# SCH_Shape-Of-Sound_2025-08-21.net
KiCad netlist of a schematic drawn in EasyEDA
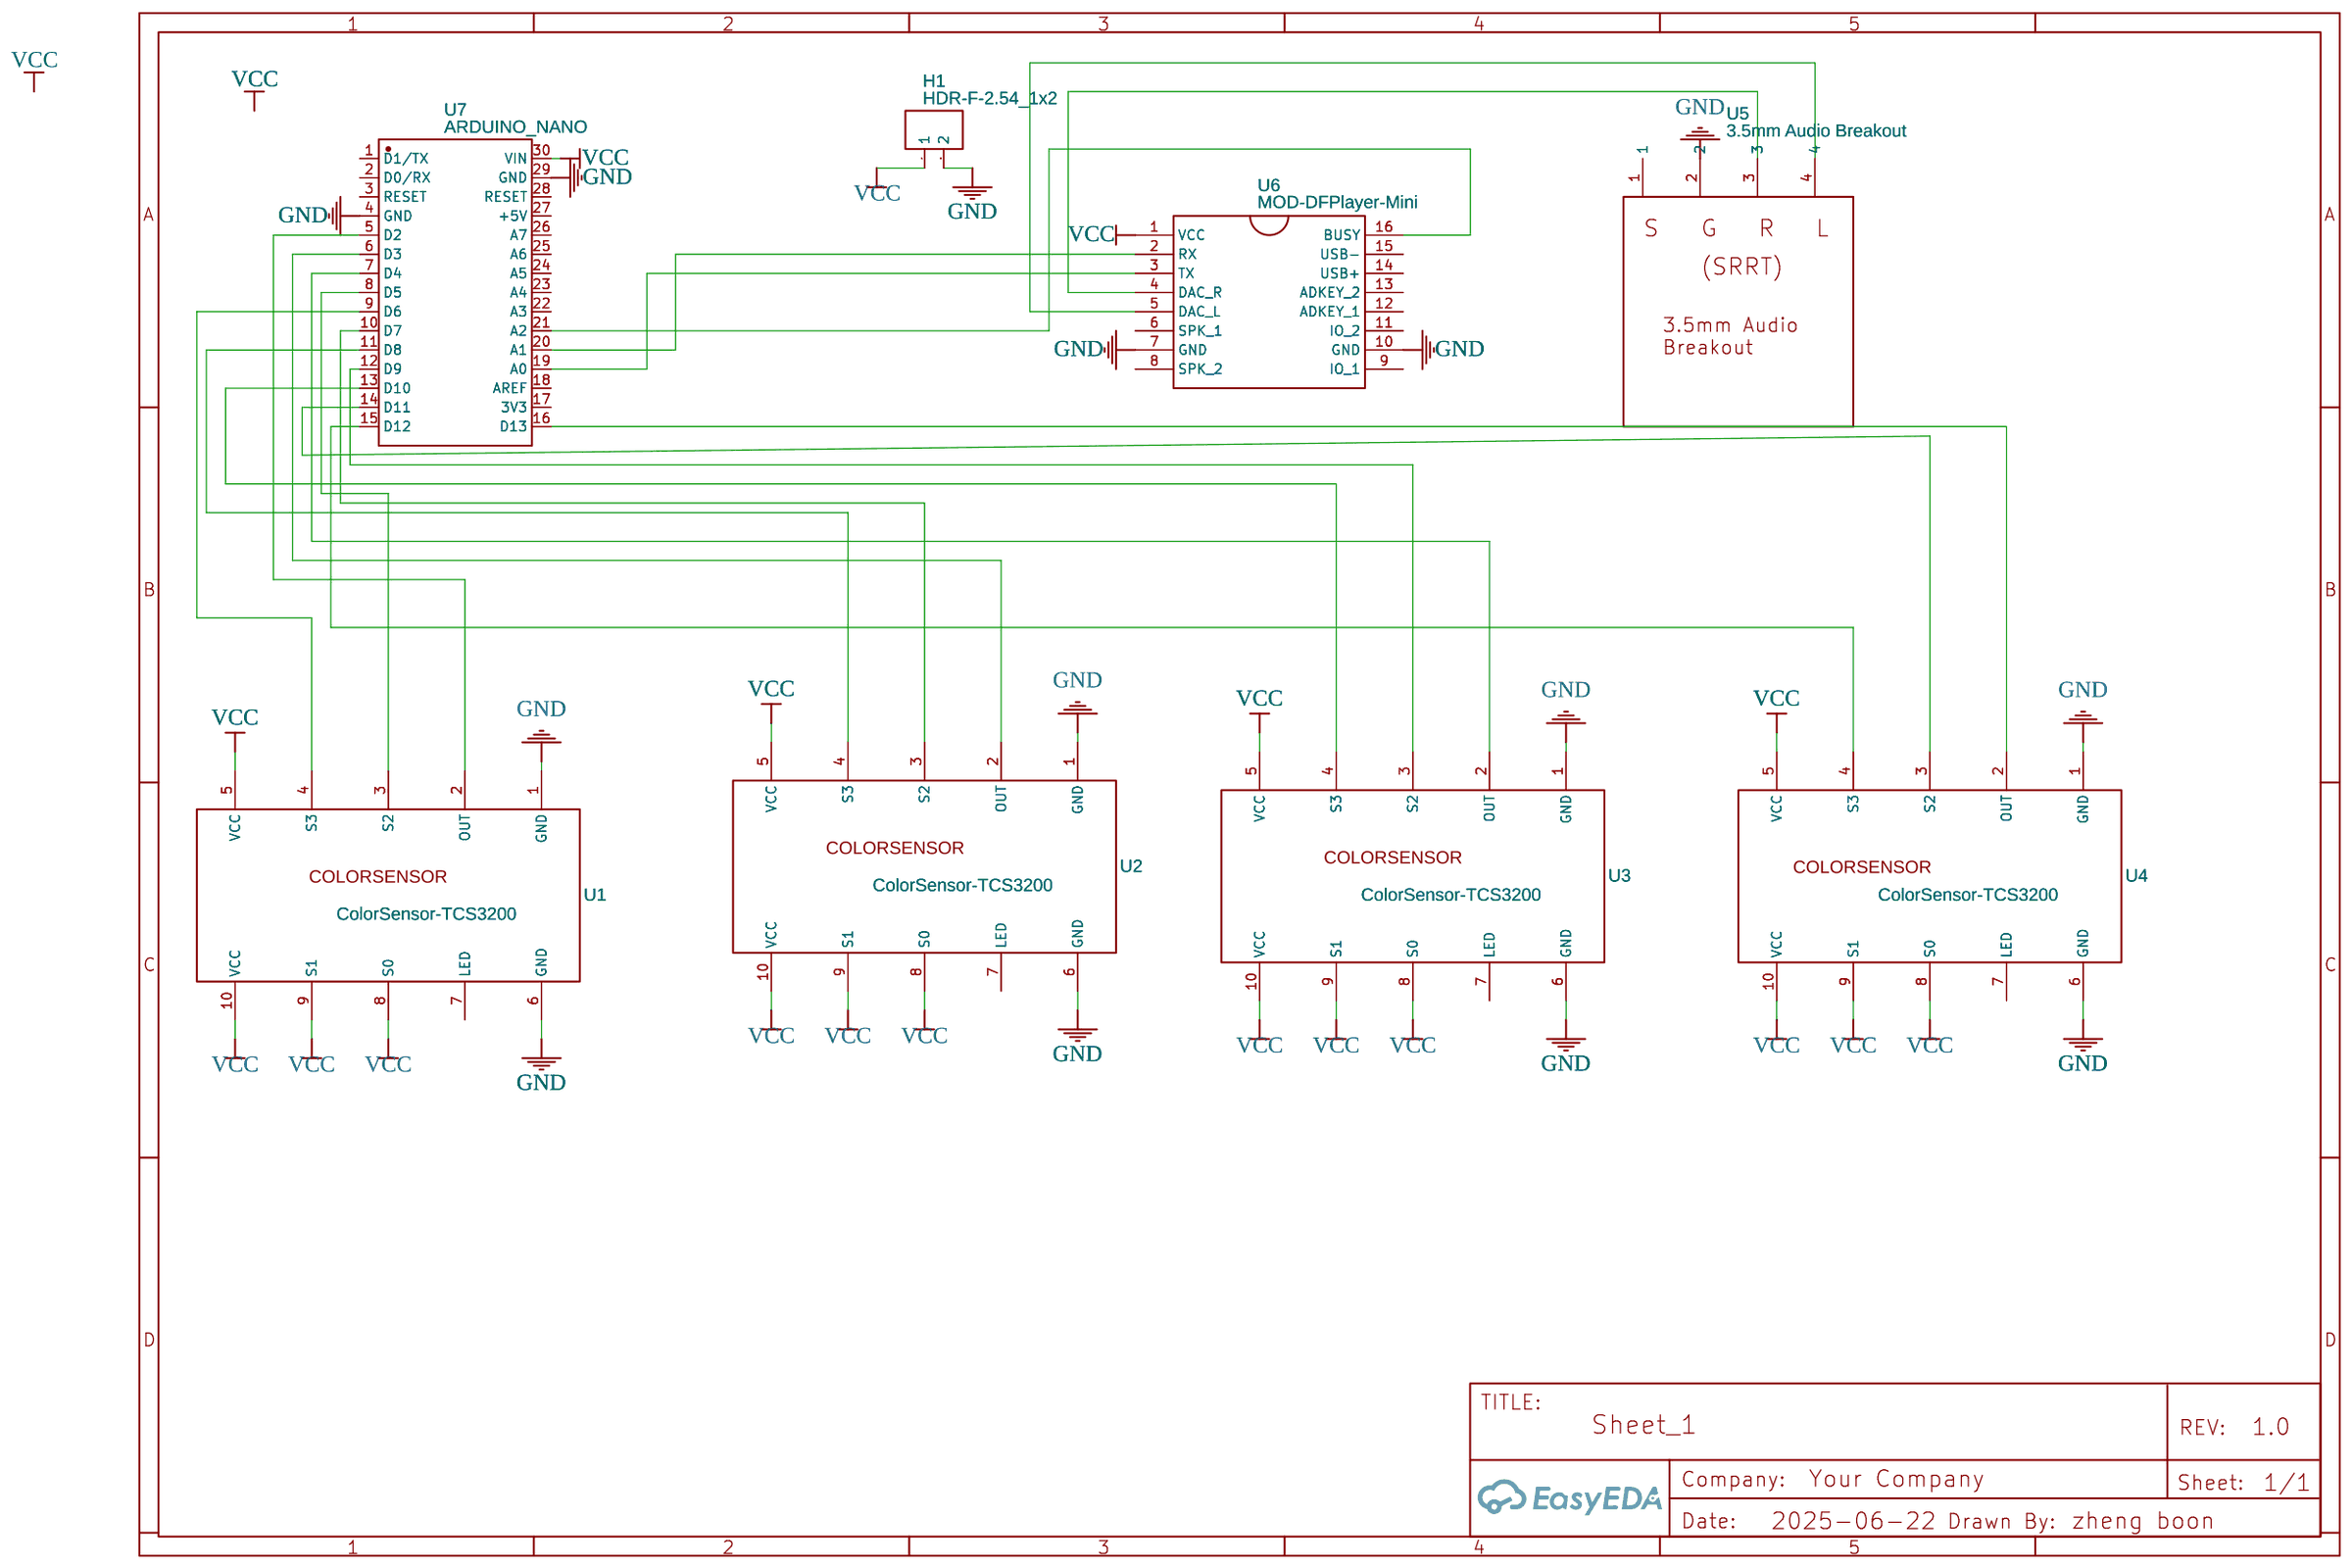
[diagram p0: schematic sheet]

(export (version "E")
  (design (tool "Eeschema 10.0.6"))
  (components
    (comp (ref "H1") (value "HDR-F-2.54_1x2") (libsource (lib "") (part "HDR-F-2.54_1x2")))
    (comp (ref "U1")
      (value "ColorSensor-TCS3200")
      (fields (field (name "Manufacturer Part") "TCS230"))
      (libsource (lib "") (part "ColorSensor-TCS3200_3"))
    )
    (comp (ref "U2")
      (value "ColorSensor-TCS3200")
      (fields (field (name "Manufacturer Part") "TCS230"))
      (libsource (lib "") (part "ColorSensor-TCS3200_2"))
    )
    (comp (ref "U3")
      (value "ColorSensor-TCS3200")
      (fields (field (name "Manufacturer Part") "TCS230"))
      (libsource (lib "") (part "ColorSensor-TCS3200_1"))
    )
    (comp (ref "U4")
      (value "ColorSensor-TCS3200")
      (fields (field (name "Manufacturer Part") "TCS230"))
      (libsource (lib "") (part "ColorSensor-TCS3200"))
    )
    (comp (ref "U5") (value "3.5mm Audio Breakout") (libsource (lib "") (part "3.5mm Audio Breakout")))
    (comp (ref "U6") (value "MOD-DFPlayer-Mini") (libsource (lib "") (part "MOD-DFPlayer-Mini")))
    (comp (ref "U7") (value "ARDUINO_NANO") (libsource (lib "") (part "ARDUINO_NANO")))
  )
  (nets
    (net (code "1") (name "GND") (class "Default")
      (node (ref "H1") (pin "2") (pinfunction "2_2") (pintype "input"))
      (node (ref "U1") (pin "1") (pinfunction "GND_1") (pintype "unspecified"))
      (node (ref "U1") (pin "6") (pinfunction "GND_6") (pintype "unspecified"))
      (node (ref "U2") (pin "1") (pinfunction "GND_1") (pintype "unspecified"))
      (node (ref "U2") (pin "6") (pinfunction "GND_6") (pintype "unspecified"))
      (node (ref "U3") (pin "1") (pinfunction "GND_1") (pintype "unspecified"))
      (node (ref "U3") (pin "6") (pinfunction "GND_6") (pintype "unspecified"))
      (node (ref "U4") (pin "1") (pinfunction "GND_1") (pintype "unspecified"))
      (node (ref "U4") (pin "6") (pinfunction "GND_6") (pintype "unspecified"))
      (node (ref "U5") (pin "2") (pinfunction "2_2") (pintype "unspecified"))
      (node (ref "U6") (pin "10") (pinfunction "GND_10") (pintype "unspecified"))
      (node (ref "U6") (pin "7") (pinfunction "GND_7") (pintype "unspecified"))
      (node (ref "U7") (pin "29") (pinfunction "GND_29") (pintype "unspecified"))
      (node (ref "U7") (pin "4") (pinfunction "GND_4") (pintype "unspecified"))
    )
    (net (code "2") (name "Net-(U1-OUT)") (class "Default")
      (node (ref "U1") (pin "2") (pinfunction "OUT_2") (pintype "unspecified"))
      (node (ref "U7") (pin "5") (pinfunction "D2_5") (pintype "unspecified"))
    )
    (net (code "3") (name "Net-(U1-S2)") (class "Default")
      (node (ref "U1") (pin "3") (pinfunction "S2_3") (pintype "unspecified"))
      (node (ref "U7") (pin "8") (pinfunction "D5_8") (pintype "unspecified"))
    )
    (net (code "4") (name "Net-(U1-S3)") (class "Default")
      (node (ref "U1") (pin "4") (pinfunction "S3_4") (pintype "unspecified"))
      (node (ref "U7") (pin "9") (pinfunction "D6_9") (pintype "unspecified"))
    )
    (net (code "5") (name "Net-(U2-OUT)") (class "Default")
      (node (ref "U2") (pin "2") (pinfunction "OUT_2") (pintype "unspecified"))
      (node (ref "U7") (pin "6") (pinfunction "D3_6") (pintype "unspecified"))
    )
    (net (code "6") (name "Net-(U2-S2)") (class "Default")
      (node (ref "U2") (pin "3") (pinfunction "S2_3") (pintype "unspecified"))
      (node (ref "U7") (pin "10") (pinfunction "D7_10") (pintype "unspecified"))
    )
    (net (code "7") (name "Net-(U2-S3)") (class "Default")
      (node (ref "U2") (pin "4") (pinfunction "S3_4") (pintype "unspecified"))
      (node (ref "U7") (pin "11") (pinfunction "D8_11") (pintype "unspecified"))
    )
    (net (code "8") (name "Net-(U3-OUT)") (class "Default")
      (node (ref "U3") (pin "2") (pinfunction "OUT_2") (pintype "unspecified"))
      (node (ref "U7") (pin "7") (pinfunction "D4_7") (pintype "unspecified"))
    )
    (net (code "9") (name "Net-(U3-S2)") (class "Default")
      (node (ref "U3") (pin "3") (pinfunction "S2_3") (pintype "unspecified"))
      (node (ref "U7") (pin "12") (pinfunction "D9_12") (pintype "unspecified"))
    )
    (net (code "10") (name "Net-(U3-S3)") (class "Default")
      (node (ref "U3") (pin "4") (pinfunction "S3_4") (pintype "unspecified"))
      (node (ref "U7") (pin "13") (pinfunction "D10_13") (pintype "unspecified"))
    )
    (net (code "11") (name "Net-(U4-OUT)") (class "Default")
      (node (ref "U4") (pin "2") (pinfunction "OUT_2") (pintype "unspecified"))
      (node (ref "U7") (pin "16") (pinfunction "D13_16") (pintype "unspecified"))
    )
    (net (code "12") (name "Net-(U4-S2)") (class "Default")
      (node (ref "U4") (pin "3") (pinfunction "S2_3") (pintype "unspecified"))
      (node (ref "U7") (pin "14") (pinfunction "D11_14") (pintype "unspecified"))
    )
    (net (code "13") (name "Net-(U4-S3)") (class "Default")
      (node (ref "U4") (pin "4") (pinfunction "S3_4") (pintype "unspecified"))
      (node (ref "U7") (pin "15") (pinfunction "D12_15") (pintype "unspecified"))
    )
    (net (code "14") (name "Net-(U6-BUSY)") (class "Default")
      (node (ref "U6") (pin "16") (pinfunction "BUSY_16") (pintype "unspecified"))
      (node (ref "U7") (pin "21") (pinfunction "A2_21") (pintype "unspecified"))
    )
    (net (code "15") (name "Net-(U6-DAC_L)") (class "Default")
      (node (ref "U5") (pin "4") (pinfunction "4_4") (pintype "unspecified"))
      (node (ref "U6") (pin "5") (pinfunction "DAC_L_5") (pintype "unspecified"))
    )
    (net (code "16") (name "Net-(U6-DAC_R)") (class "Default")
      (node (ref "U5") (pin "3") (pinfunction "3_3") (pintype "unspecified"))
      (node (ref "U6") (pin "4") (pinfunction "DAC_R_4") (pintype "unspecified"))
    )
    (net (code "17") (name "Net-(U6-RX)") (class "Default")
      (node (ref "U6") (pin "2") (pinfunction "RX_2") (pintype "unspecified"))
      (node (ref "U7") (pin "20") (pinfunction "A1_20") (pintype "unspecified"))
    )
    (net (code "18") (name "Net-(U6-TX)") (class "Default")
      (node (ref "U6") (pin "3") (pinfunction "TX_3") (pintype "unspecified"))
      (node (ref "U7") (pin "19") (pinfunction "A0_19") (pintype "unspecified"))
    )
    (net (code "19") (name "VCC") (class "Default")
      (node (ref "H1") (pin "1") (pinfunction "1_1") (pintype "input"))
      (node (ref "U1") (pin "10") (pinfunction "VCC_10") (pintype "unspecified"))
      (node (ref "U1") (pin "5") (pinfunction "VCC_5") (pintype "unspecified"))
      (node (ref "U1") (pin "8") (pinfunction "S0_8") (pintype "unspecified"))
      (node (ref "U1") (pin "9") (pinfunction "S1_9") (pintype "unspecified"))
      (node (ref "U2") (pin "10") (pinfunction "VCC_10") (pintype "unspecified"))
      (node (ref "U2") (pin "5") (pinfunction "VCC_5") (pintype "unspecified"))
      (node (ref "U2") (pin "8") (pinfunction "S0_8") (pintype "unspecified"))
      (node (ref "U2") (pin "9") (pinfunction "S1_9") (pintype "unspecified"))
      (node (ref "U3") (pin "10") (pinfunction "VCC_10") (pintype "unspecified"))
      (node (ref "U3") (pin "5") (pinfunction "VCC_5") (pintype "unspecified"))
      (node (ref "U3") (pin "8") (pinfunction "S0_8") (pintype "unspecified"))
      (node (ref "U3") (pin "9") (pinfunction "S1_9") (pintype "unspecified"))
      (node (ref "U4") (pin "10") (pinfunction "VCC_10") (pintype "unspecified"))
      (node (ref "U4") (pin "5") (pinfunction "VCC_5") (pintype "unspecified"))
      (node (ref "U4") (pin "8") (pinfunction "S0_8") (pintype "unspecified"))
      (node (ref "U4") (pin "9") (pinfunction "S1_9") (pintype "unspecified"))
      (node (ref "U6") (pin "1") (pinfunction "VCC_1") (pintype "unspecified"))
      (node (ref "U7") (pin "30") (pinfunction "VIN_30") (pintype "unspecified"))
    )
    (net (code "20") (name "unconnected-(U1-LED-Pad7)") (class "Default")
      (node (ref "U1") (pin "7") (pinfunction "LED_7") (pintype "unspecified"))
    )
    (net (code "21") (name "unconnected-(U2-LED-Pad7)") (class "Default")
      (node (ref "U2") (pin "7") (pinfunction "LED_7") (pintype "unspecified"))
    )
    (net (code "22") (name "unconnected-(U3-LED-Pad7)") (class "Default")
      (node (ref "U3") (pin "7") (pinfunction "LED_7") (pintype "unspecified"))
    )
    (net (code "23") (name "unconnected-(U4-LED-Pad7)") (class "Default")
      (node (ref "U4") (pin "7") (pinfunction "LED_7") (pintype "unspecified"))
    )
    (net (code "24") (name "unconnected-(U5-Pad1)") (class "Default")
      (node (ref "U5") (pin "1") (pinfunction "1_1") (pintype "unspecified"))
    )
    (net (code "25") (name "unconnected-(U6-ADKEY_1-Pad12)") (class "Default")
      (node (ref "U6") (pin "12") (pinfunction "ADKEY_1_12") (pintype "unspecified"))
    )
    (net (code "26") (name "unconnected-(U6-ADKEY_2-Pad13)") (class "Default")
      (node (ref "U6") (pin "13") (pinfunction "ADKEY_2_13") (pintype "unspecified"))
    )
    (net (code "27") (name "unconnected-(U6-IO_1-Pad9)") (class "Default")
      (node (ref "U6") (pin "9") (pinfunction "IO_1_9") (pintype "unspecified"))
    )
    (net (code "28") (name "unconnected-(U6-IO_2-Pad11)") (class "Default")
      (node (ref "U6") (pin "11") (pinfunction "IO_2_11") (pintype "unspecified"))
    )
    (net (code "29") (name "unconnected-(U6-SPK_1-Pad6)") (class "Default")
      (node (ref "U6") (pin "6") (pinfunction "SPK_1_6") (pintype "unspecified"))
    )
    (net (code "30") (name "unconnected-(U6-SPK_2-Pad8)") (class "Default")
      (node (ref "U6") (pin "8") (pinfunction "SPK_2_8") (pintype "unspecified"))
    )
    (net (code "31") (name "unconnected-(U6-USB+-Pad14)") (class "Default")
      (node (ref "U6") (pin "14") (pinfunction "USB+_14") (pintype "unspecified"))
    )
    (net (code "32") (name "unconnected-(U6-USB--Pad15)") (class "Default")
      (node (ref "U6") (pin "15") (pinfunction "USB-_15") (pintype "unspecified"))
    )
    (net (code "33") (name "unconnected-(U7-+5V-Pad27)") (class "Default")
      (node (ref "U7") (pin "27") (pinfunction "+5V_27") (pintype "unspecified"))
    )
    (net (code "34") (name "unconnected-(U7-3V3-Pad17)") (class "Default")
      (node (ref "U7") (pin "17") (pinfunction "3V3_17") (pintype "unspecified"))
    )
    (net (code "35") (name "unconnected-(U7-A3-Pad22)") (class "Default")
      (node (ref "U7") (pin "22") (pinfunction "A3_22") (pintype "unspecified"))
    )
    (net (code "36") (name "unconnected-(U7-A4-Pad23)") (class "Default")
      (node (ref "U7") (pin "23") (pinfunction "A4_23") (pintype "unspecified"))
    )
    (net (code "37") (name "unconnected-(U7-A5-Pad24)") (class "Default")
      (node (ref "U7") (pin "24") (pinfunction "A5_24") (pintype "unspecified"))
    )
    (net (code "38") (name "unconnected-(U7-A6-Pad25)") (class "Default")
      (node (ref "U7") (pin "25") (pinfunction "A6_25") (pintype "unspecified"))
    )
    (net (code "39") (name "unconnected-(U7-A7-Pad26)") (class "Default")
      (node (ref "U7") (pin "26") (pinfunction "A7_26") (pintype "unspecified"))
    )
    (net (code "40") (name "unconnected-(U7-AREF-Pad18)") (class "Default")
      (node (ref "U7") (pin "18") (pinfunction "AREF_18") (pintype "unspecified"))
    )
    (net (code "41") (name "unconnected-(U7-D0{slash}RX-Pad2)") (class "Default")
      (node (ref "U7") (pin "2") (pinfunction "D0/RX_2") (pintype "unspecified"))
    )
    (net (code "42") (name "unconnected-(U7-D1{slash}TX-Pad1)") (class "Default")
      (node (ref "U7") (pin "1") (pinfunction "D1/TX_1") (pintype "unspecified"))
    )
    (net (code "43") (name "unconnected-(U7-RESET-Pad3)") (class "Default")
      (node (ref "U7") (pin "3") (pinfunction "RESET_3") (pintype "unspecified"))
    )
    (net (code "44") (name "unconnected-(U7-RESET-Pad28)") (class "Default")
      (node (ref "U7") (pin "28") (pinfunction "RESET_28") (pintype "unspecified"))
    )
  )
)
